# Ring_v1_0.net
KiCad netlist of a schematic drawn in EAGLE
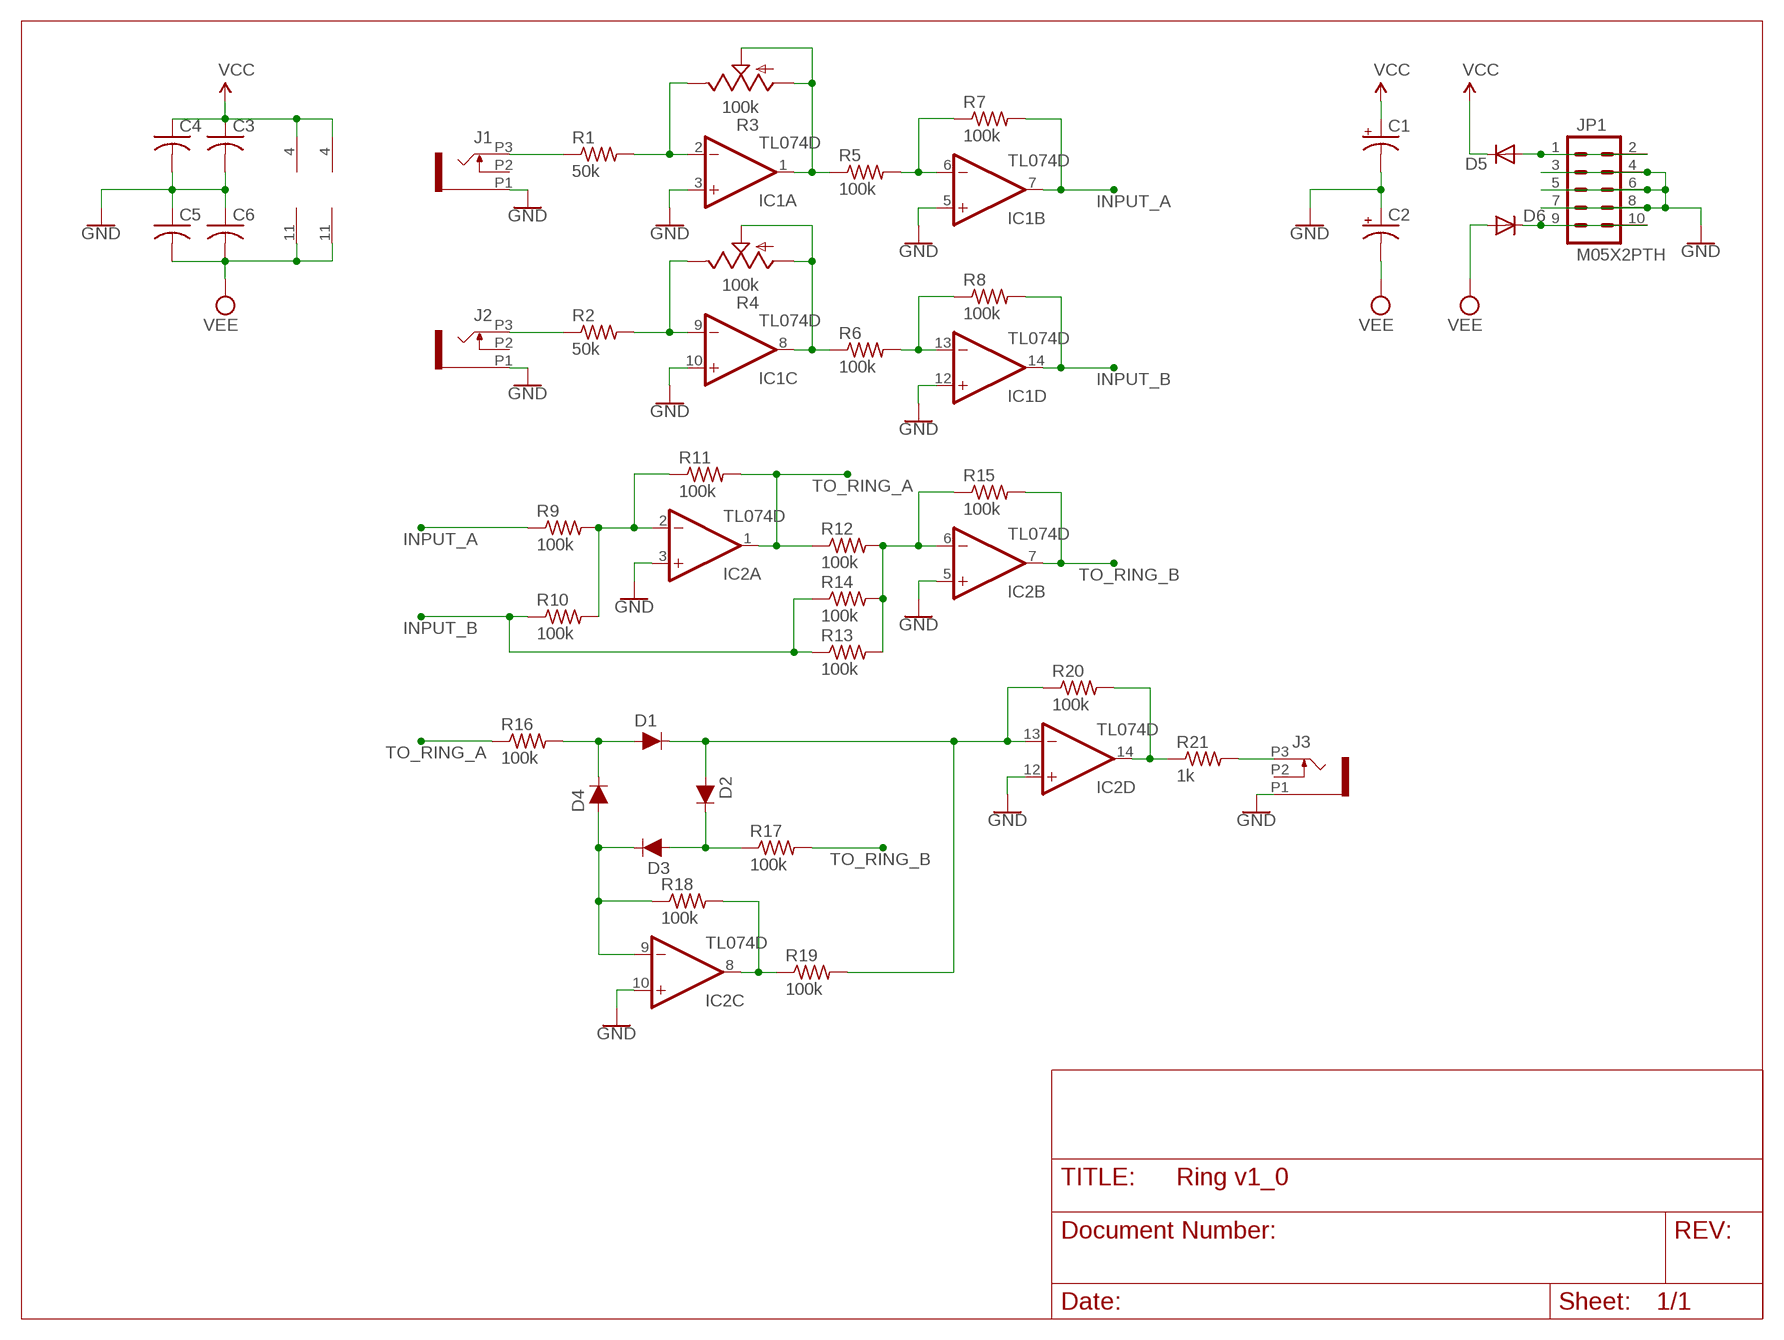
[diagram p0: schematic, sheet 1]

(export (version "E")
  (design (tool "Eeschema 10.0.6"))
  (components
    (comp (ref "C1")
      (value "RCL_CPOL-USB")
      (footprint "eagle-import:RCL_PANASONIC_B")
      (libsource (lib "eagle-import") (part "RCL_CPOL-USB"))
    )
    (comp (ref "C2")
      (value "RCL_CPOL-USB")
      (footprint "eagle-import:RCL_PANASONIC_B")
      (libsource (lib "eagle-import") (part "RCL_CPOL-USB"))
    )
    (comp (ref "C3")
      (value "RCL_C-USC0603")
      (footprint "eagle-import:RCL_C0603")
      (libsource (lib "eagle-import") (part "RCL_C-USC0603"))
    )
    (comp (ref "C4")
      (value "RCL_C-USC0603")
      (footprint "eagle-import:RCL_C0603")
      (libsource (lib "eagle-import") (part "RCL_C-USC0603"))
    )
    (comp (ref "C5")
      (value "RCL_C-USC0603")
      (footprint "eagle-import:RCL_C0603")
      (libsource (lib "eagle-import") (part "RCL_C-USC0603"))
    )
    (comp (ref "C6")
      (value "RCL_C-USC0603")
      (footprint "eagle-import:RCL_C0603")
      (libsource (lib "eagle-import") (part "RCL_C-USC0603"))
    )
    (comp (ref "D1")
      (value "DIODE-PTH")
      (footprint "eagle-import:DIODE-1N4001")
      (libsource (lib "eagle-import") (part "DIODE-PTH"))
    )
    (comp (ref "D2")
      (value "DIODE-PTH")
      (footprint "eagle-import:DIODE-1N4001")
      (libsource (lib "eagle-import") (part "DIODE-PTH"))
    )
    (comp (ref "D3")
      (value "DIODE-PTH")
      (footprint "eagle-import:DIODE-1N4001")
      (libsource (lib "eagle-import") (part "DIODE-PTH"))
    )
    (comp (ref "D4")
      (value "DIODE-PTH")
      (footprint "eagle-import:DIODE-1N4001")
      (libsource (lib "eagle-import") (part "DIODE-PTH"))
    )
    (comp (ref "D5")
      (value "DIODE_DIODE-SOD123")
      (footprint "eagle-import:DIODE_SOD123")
      (libsource (lib "eagle-import") (part "DIODE_DIODE-SOD123"))
    )
    (comp (ref "D6")
      (value "DIODE_DIODE-SOD123")
      (footprint "eagle-import:DIODE_SOD123")
      (libsource (lib "eagle-import") (part "DIODE_DIODE-SOD123"))
    )
    (comp (ref "IC1")
      (value "TL074D")
      (footprint "eagle-import:SO14")
      (libsource (lib "eagle-import") (part "TL074D"))
    )
    (comp (ref "IC2")
      (value "TL074D")
      (footprint "eagle-import:SO14")
      (libsource (lib "eagle-import") (part "TL074D"))
    )
    (comp (ref "J1")
      (value "OG-PJ301_PJ301_THONKICONN8")
      (footprint "eagle-import:OG-PJ301_WQP_PJ_301M8")
      (libsource (lib "eagle-import") (part "OG-PJ301_PJ301_THONKICONN8"))
    )
    (comp (ref "J2")
      (value "OG-PJ301_PJ301_THONKICONN8")
      (footprint "eagle-import:OG-PJ301_WQP_PJ_301M8")
      (libsource (lib "eagle-import") (part "OG-PJ301_PJ301_THONKICONN8"))
    )
    (comp (ref "J3")
      (value "OG-PJ301_PJ301_THONKICONN8")
      (footprint "eagle-import:OG-PJ301_WQP_PJ_301M8")
      (libsource (lib "eagle-import") (part "OG-PJ301_PJ301_THONKICONN8"))
    )
    (comp (ref "JP1")
      (value "M05X2PTH")
      (footprint "eagle-import:OG-HEADER_AVR_ICSP")
      (libsource (lib "eagle-import") (part "OG-HEADER_M05X2PTH"))
    )
    (comp (ref "R1")
      (value "50k")
      (footprint "eagle-import:RESISTOR_R0603")
      (libsource (lib "eagle-import") (part "RESISTOR_R-US_R0603"))
    )
    (comp (ref "R2")
      (value "50k")
      (footprint "eagle-import:RESISTOR_R0603")
      (libsource (lib "eagle-import") (part "RESISTOR_R-US_R0603"))
    )
    (comp (ref "R3")
      (value "100k")
      (footprint "eagle-import:POT-ALPS_ALPS_POT_VERTICAL_PS2")
      (libsource (lib "eagle-import") (part "POT-ALPS_POT_USVERTICAL_PS2"))
    )
    (comp (ref "R4")
      (value "100k")
      (footprint "eagle-import:POT-ALPS_ALPS_POT_VERTICAL_PS2")
      (libsource (lib "eagle-import") (part "POT-ALPS_POT_USVERTICAL_PS2"))
    )
    (comp (ref "R5")
      (value "100k")
      (footprint "eagle-import:RESISTOR_R0603")
      (libsource (lib "eagle-import") (part "RESISTOR_R-US_R0603"))
    )
    (comp (ref "R6")
      (value "100k")
      (footprint "eagle-import:RESISTOR_R0603")
      (libsource (lib "eagle-import") (part "RESISTOR_R-US_R0603"))
    )
    (comp (ref "R7")
      (value "100k")
      (footprint "eagle-import:RESISTOR_R0603")
      (libsource (lib "eagle-import") (part "RESISTOR_R-US_R0603"))
    )
    (comp (ref "R8")
      (value "100k")
      (footprint "eagle-import:RESISTOR_R0603")
      (libsource (lib "eagle-import") (part "RESISTOR_R-US_R0603"))
    )
    (comp (ref "R9")
      (value "100k")
      (footprint "eagle-import:RESISTOR_R0603")
      (libsource (lib "eagle-import") (part "RESISTOR_R-US_R0603"))
    )
    (comp (ref "R10")
      (value "100k")
      (footprint "eagle-import:RESISTOR_R0603")
      (libsource (lib "eagle-import") (part "RESISTOR_R-US_R0603"))
    )
    (comp (ref "R11")
      (value "100k")
      (footprint "eagle-import:RESISTOR_R0603")
      (libsource (lib "eagle-import") (part "RESISTOR_R-US_R0603"))
    )
    (comp (ref "R12")
      (value "100k")
      (footprint "eagle-import:RESISTOR_R0603")
      (libsource (lib "eagle-import") (part "RESISTOR_R-US_R0603"))
    )
    (comp (ref "R13")
      (value "100k")
      (footprint "eagle-import:RESISTOR_R0603")
      (libsource (lib "eagle-import") (part "RESISTOR_R-US_R0603"))
    )
    (comp (ref "R14")
      (value "100k")
      (footprint "eagle-import:RESISTOR_R0603")
      (libsource (lib "eagle-import") (part "RESISTOR_R-US_R0603"))
    )
    (comp (ref "R15")
      (value "100k")
      (footprint "eagle-import:RESISTOR_R0603")
      (libsource (lib "eagle-import") (part "RESISTOR_R-US_R0603"))
    )
    (comp (ref "R16")
      (value "100k")
      (footprint "eagle-import:RESISTOR_R0603")
      (libsource (lib "eagle-import") (part "RESISTOR_R-US_R0603"))
    )
    (comp (ref "R17")
      (value "100k")
      (footprint "eagle-import:RESISTOR_R0603")
      (libsource (lib "eagle-import") (part "RESISTOR_R-US_R0603"))
    )
    (comp (ref "R18")
      (value "100k")
      (footprint "eagle-import:RESISTOR_R0603")
      (libsource (lib "eagle-import") (part "RESISTOR_R-US_R0603"))
    )
    (comp (ref "R19")
      (value "100k")
      (footprint "eagle-import:RESISTOR_R0603")
      (libsource (lib "eagle-import") (part "RESISTOR_R-US_R0603"))
    )
    (comp (ref "R20")
      (value "100k")
      (footprint "eagle-import:RESISTOR_R0603")
      (libsource (lib "eagle-import") (part "RESISTOR_R-US_R0603"))
    )
    (comp (ref "R21")
      (value "1k")
      (footprint "eagle-import:RESISTOR_R0603")
      (libsource (lib "eagle-import") (part "RESISTOR_R-US_R0603"))
    )
  )
  (nets
    (net (code "1") (name "/INPUT_A") (class "Default")
      (node (ref "IC1") (pin "7") (pinfunction "OUT_7") (pintype "output"))
      (node (ref "R7") (pin "2") (pinfunction "2_2") (pintype "passive"))
      (node (ref "R9") (pin "1") (pinfunction "1_1") (pintype "passive"))
    )
    (net (code "2") (name "/INPUT_B") (class "Default")
      (node (ref "IC1") (pin "14") (pinfunction "OUT_14") (pintype "output"))
      (node (ref "R10") (pin "1") (pinfunction "1_1") (pintype "passive"))
      (node (ref "R13") (pin "1") (pinfunction "1_1") (pintype "passive"))
      (node (ref "R14") (pin "1") (pinfunction "1_1") (pintype "passive"))
      (node (ref "R8") (pin "2") (pinfunction "2_2") (pintype "passive"))
    )
    (net (code "3") (name "/TO_RING_A") (class "Default")
      (node (ref "IC2") (pin "1") (pinfunction "OUT_1") (pintype "output"))
      (node (ref "R11") (pin "2") (pinfunction "2_2") (pintype "passive"))
      (node (ref "R12") (pin "1") (pinfunction "1_1") (pintype "passive"))
      (node (ref "R16") (pin "1") (pinfunction "1_1") (pintype "passive"))
    )
    (net (code "4") (name "/TO_RING_B") (class "Default")
      (node (ref "IC2") (pin "7") (pinfunction "OUT_7") (pintype "output"))
      (node (ref "R15") (pin "2") (pinfunction "2_2") (pintype "passive"))
      (node (ref "R17") (pin "2") (pinfunction "2_2") (pintype "passive"))
    )
    (net (code "5") (name "GND") (class "Default")
      (node (ref "C1") (pin "-") (pinfunction "-_-") (pintype "passive"))
      (node (ref "C2") (pin "+") (pinfunction "+_+") (pintype "passive"))
      (node (ref "C3") (pin "2") (pinfunction "2_2") (pintype "passive"))
      (node (ref "C4") (pin "2") (pinfunction "2_2") (pintype "passive"))
      (node (ref "C5") (pin "1") (pinfunction "1_1") (pintype "passive"))
      (node (ref "C6") (pin "1") (pinfunction "1_1") (pintype "passive"))
      (node (ref "IC1") (pin "10") (pinfunction "+IN_10") (pintype "input"))
      (node (ref "IC1") (pin "12") (pinfunction "+IN_12") (pintype "input"))
      (node (ref "IC1") (pin "3") (pinfunction "+IN_3") (pintype "input"))
      (node (ref "IC1") (pin "5") (pinfunction "+IN_5") (pintype "input"))
      (node (ref "IC2") (pin "10") (pinfunction "+IN_10") (pintype "input"))
      (node (ref "IC2") (pin "12") (pinfunction "+IN_12") (pintype "input"))
      (node (ref "IC2") (pin "3") (pinfunction "+IN_3") (pintype "input"))
      (node (ref "IC2") (pin "5") (pinfunction "+IN_5") (pintype "input"))
      (node (ref "J1") (pin "P1") (pinfunction "1_P1") (pintype "passive"))
      (node (ref "J2") (pin "P1") (pinfunction "1_P1") (pintype "passive"))
      (node (ref "J3") (pin "P1") (pinfunction "1_P1") (pintype "passive"))
      (node (ref "JP1") (pin "3") (pinfunction "3_3") (pintype "passive"))
      (node (ref "JP1") (pin "4") (pinfunction "4_4") (pintype "passive"))
      (node (ref "JP1") (pin "5") (pinfunction "5_5") (pintype "passive"))
      (node (ref "JP1") (pin "6") (pinfunction "6_6") (pintype "passive"))
      (node (ref "JP1") (pin "7") (pinfunction "7_7") (pintype "passive"))
      (node (ref "JP1") (pin "8") (pinfunction "8_8") (pintype "passive"))
    )
    (net (code "6") (name "Net-(D1-PadA)") (class "Default")
      (node (ref "D1") (pin "A") (pinfunction "A_A") (pintype "passive"))
      (node (ref "D4") (pin "C") (pinfunction "C_C") (pintype "passive"))
      (node (ref "R16") (pin "2") (pinfunction "2_2") (pintype "passive"))
    )
    (net (code "7") (name "Net-(D2-PadC)") (class "Default")
      (node (ref "D2") (pin "C") (pinfunction "C_C") (pintype "passive"))
      (node (ref "D3") (pin "A") (pinfunction "A_A") (pintype "passive"))
      (node (ref "R17") (pin "1") (pinfunction "1_1") (pintype "passive"))
    )
    (net (code "8") (name "Net-(D5-PadA)") (class "Default")
      (node (ref "D5") (pin "A") (pinfunction "A_A") (pintype "passive"))
      (node (ref "JP1") (pin "1") (pinfunction "1_1") (pintype "passive"))
      (node (ref "JP1") (pin "2") (pinfunction "2_2") (pintype "passive"))
    )
    (net (code "9") (name "Net-(D6-PadC)") (class "Default")
      (node (ref "D6") (pin "C") (pinfunction "C_C") (pintype "passive"))
      (node (ref "JP1") (pin "10") (pinfunction "10_10") (pintype "passive"))
      (node (ref "JP1") (pin "9") (pinfunction "9_9") (pintype "passive"))
    )
    (net (code "10") (name "Net-(IC1A--IN)") (class "Default")
      (node (ref "IC1") (pin "2") (pinfunction "-IN_2") (pintype "input"))
      (node (ref "R1") (pin "2") (pinfunction "2_2") (pintype "passive"))
      (node (ref "R3") (pin "P$1") (pinfunction "E_P$1") (pintype "passive"))
    )
    (net (code "11") (name "Net-(IC1A-OUT)") (class "Default")
      (node (ref "IC1") (pin "1") (pinfunction "OUT_1") (pintype "output"))
      (node (ref "R3") (pin "P$2") (pinfunction "S_P$2") (pintype "passive"))
      (node (ref "R3") (pin "P$3") (pinfunction "A_P$3") (pintype "passive"))
      (node (ref "R5") (pin "1") (pinfunction "1_1") (pintype "passive"))
    )
    (net (code "12") (name "Net-(IC1B--IN)") (class "Default")
      (node (ref "IC1") (pin "6") (pinfunction "-IN_6") (pintype "input"))
      (node (ref "R5") (pin "2") (pinfunction "2_2") (pintype "passive"))
      (node (ref "R7") (pin "1") (pinfunction "1_1") (pintype "passive"))
    )
    (net (code "13") (name "Net-(IC1C--IN)") (class "Default")
      (node (ref "IC1") (pin "9") (pinfunction "-IN_9") (pintype "input"))
      (node (ref "R2") (pin "2") (pinfunction "2_2") (pintype "passive"))
      (node (ref "R4") (pin "P$1") (pinfunction "E_P$1") (pintype "passive"))
    )
    (net (code "14") (name "Net-(IC1C-OUT)") (class "Default")
      (node (ref "IC1") (pin "8") (pinfunction "OUT_8") (pintype "output"))
      (node (ref "R4") (pin "P$2") (pinfunction "S_P$2") (pintype "passive"))
      (node (ref "R4") (pin "P$3") (pinfunction "A_P$3") (pintype "passive"))
      (node (ref "R6") (pin "1") (pinfunction "1_1") (pintype "passive"))
    )
    (net (code "15") (name "Net-(IC1D--IN)") (class "Default")
      (node (ref "IC1") (pin "13") (pinfunction "-IN_13") (pintype "input"))
      (node (ref "R6") (pin "2") (pinfunction "2_2") (pintype "passive"))
      (node (ref "R8") (pin "1") (pinfunction "1_1") (pintype "passive"))
    )
    (net (code "16") (name "Net-(IC2A--IN)") (class "Default")
      (node (ref "IC2") (pin "2") (pinfunction "-IN_2") (pintype "input"))
      (node (ref "R10") (pin "2") (pinfunction "2_2") (pintype "passive"))
      (node (ref "R11") (pin "1") (pinfunction "1_1") (pintype "passive"))
      (node (ref "R9") (pin "2") (pinfunction "2_2") (pintype "passive"))
    )
    (net (code "17") (name "Net-(IC2B--IN)") (class "Default")
      (node (ref "IC2") (pin "6") (pinfunction "-IN_6") (pintype "input"))
      (node (ref "R12") (pin "2") (pinfunction "2_2") (pintype "passive"))
      (node (ref "R13") (pin "2") (pinfunction "2_2") (pintype "passive"))
      (node (ref "R14") (pin "2") (pinfunction "2_2") (pintype "passive"))
      (node (ref "R15") (pin "1") (pinfunction "1_1") (pintype "passive"))
    )
    (net (code "18") (name "Net-(IC2C--IN)") (class "Default")
      (node (ref "D3") (pin "C") (pinfunction "C_C") (pintype "passive"))
      (node (ref "D4") (pin "A") (pinfunction "A_A") (pintype "passive"))
      (node (ref "IC2") (pin "9") (pinfunction "-IN_9") (pintype "input"))
      (node (ref "R18") (pin "1") (pinfunction "1_1") (pintype "passive"))
    )
    (net (code "19") (name "Net-(IC2C-OUT)") (class "Default")
      (node (ref "IC2") (pin "8") (pinfunction "OUT_8") (pintype "output"))
      (node (ref "R18") (pin "2") (pinfunction "2_2") (pintype "passive"))
      (node (ref "R19") (pin "1") (pinfunction "1_1") (pintype "passive"))
    )
    (net (code "20") (name "Net-(IC2D--IN)") (class "Default")
      (node (ref "D1") (pin "C") (pinfunction "C_C") (pintype "passive"))
      (node (ref "D2") (pin "A") (pinfunction "A_A") (pintype "passive"))
      (node (ref "IC2") (pin "13") (pinfunction "-IN_13") (pintype "input"))
      (node (ref "R19") (pin "2") (pinfunction "2_2") (pintype "passive"))
      (node (ref "R20") (pin "1") (pinfunction "1_1") (pintype "passive"))
    )
    (net (code "21") (name "Net-(IC2D-OUT)") (class "Default")
      (node (ref "IC2") (pin "14") (pinfunction "OUT_14") (pintype "output"))
      (node (ref "R20") (pin "2") (pinfunction "2_2") (pintype "passive"))
      (node (ref "R21") (pin "1") (pinfunction "1_1") (pintype "passive"))
    )
    (net (code "22") (name "Net-(J1-3)") (class "Default")
      (node (ref "J1") (pin "P3") (pinfunction "3_P3") (pintype "passive"))
      (node (ref "R1") (pin "1") (pinfunction "1_1") (pintype "passive"))
    )
    (net (code "23") (name "Net-(J2-3)") (class "Default")
      (node (ref "J2") (pin "P3") (pinfunction "3_P3") (pintype "passive"))
      (node (ref "R2") (pin "1") (pinfunction "1_1") (pintype "passive"))
    )
    (net (code "24") (name "Net-(J3-3)") (class "Default")
      (node (ref "J3") (pin "P3") (pinfunction "3_P3") (pintype "passive"))
      (node (ref "R21") (pin "2") (pinfunction "2_2") (pintype "passive"))
    )
    (net (code "25") (name "VCC") (class "Default")
      (node (ref "C1") (pin "+") (pinfunction "+_+") (pintype "passive"))
      (node (ref "C3") (pin "1") (pinfunction "1_1") (pintype "passive"))
      (node (ref "C4") (pin "1") (pinfunction "1_1") (pintype "passive"))
      (node (ref "D5") (pin "C") (pinfunction "C_C") (pintype "passive"))
      (node (ref "IC1") (pin "4") (pinfunction "V+_4") (pintype "power_in"))
      (node (ref "IC2") (pin "4") (pinfunction "V+_4") (pintype "power_in"))
    )
    (net (code "26") (name "VEE") (class "Default")
      (node (ref "C2") (pin "-") (pinfunction "-_-") (pintype "passive"))
      (node (ref "C5") (pin "2") (pinfunction "2_2") (pintype "passive"))
      (node (ref "C6") (pin "2") (pinfunction "2_2") (pintype "passive"))
      (node (ref "D6") (pin "A") (pinfunction "A_A") (pintype "passive"))
      (node (ref "IC1") (pin "11") (pinfunction "V-_11") (pintype "power_in"))
      (node (ref "IC2") (pin "11") (pinfunction "V-_11") (pintype "power_in"))
    )
    (net (code "27") (name "unconnected-(J1-2-PadP2)") (class "Default")
      (node (ref "J1") (pin "P2") (pinfunction "2_P2") (pintype "passive"))
    )
    (net (code "28") (name "unconnected-(J2-2-PadP2)") (class "Default")
      (node (ref "J2") (pin "P2") (pinfunction "2_P2") (pintype "passive"))
    )
    (net (code "29") (name "unconnected-(J3-2-PadP2)") (class "Default")
      (node (ref "J3") (pin "P2") (pinfunction "2_P2") (pintype "passive"))
    )
  )
)
